# Team16_FINAL.net
KiCad netlist of a schematic drawn in EAGLE
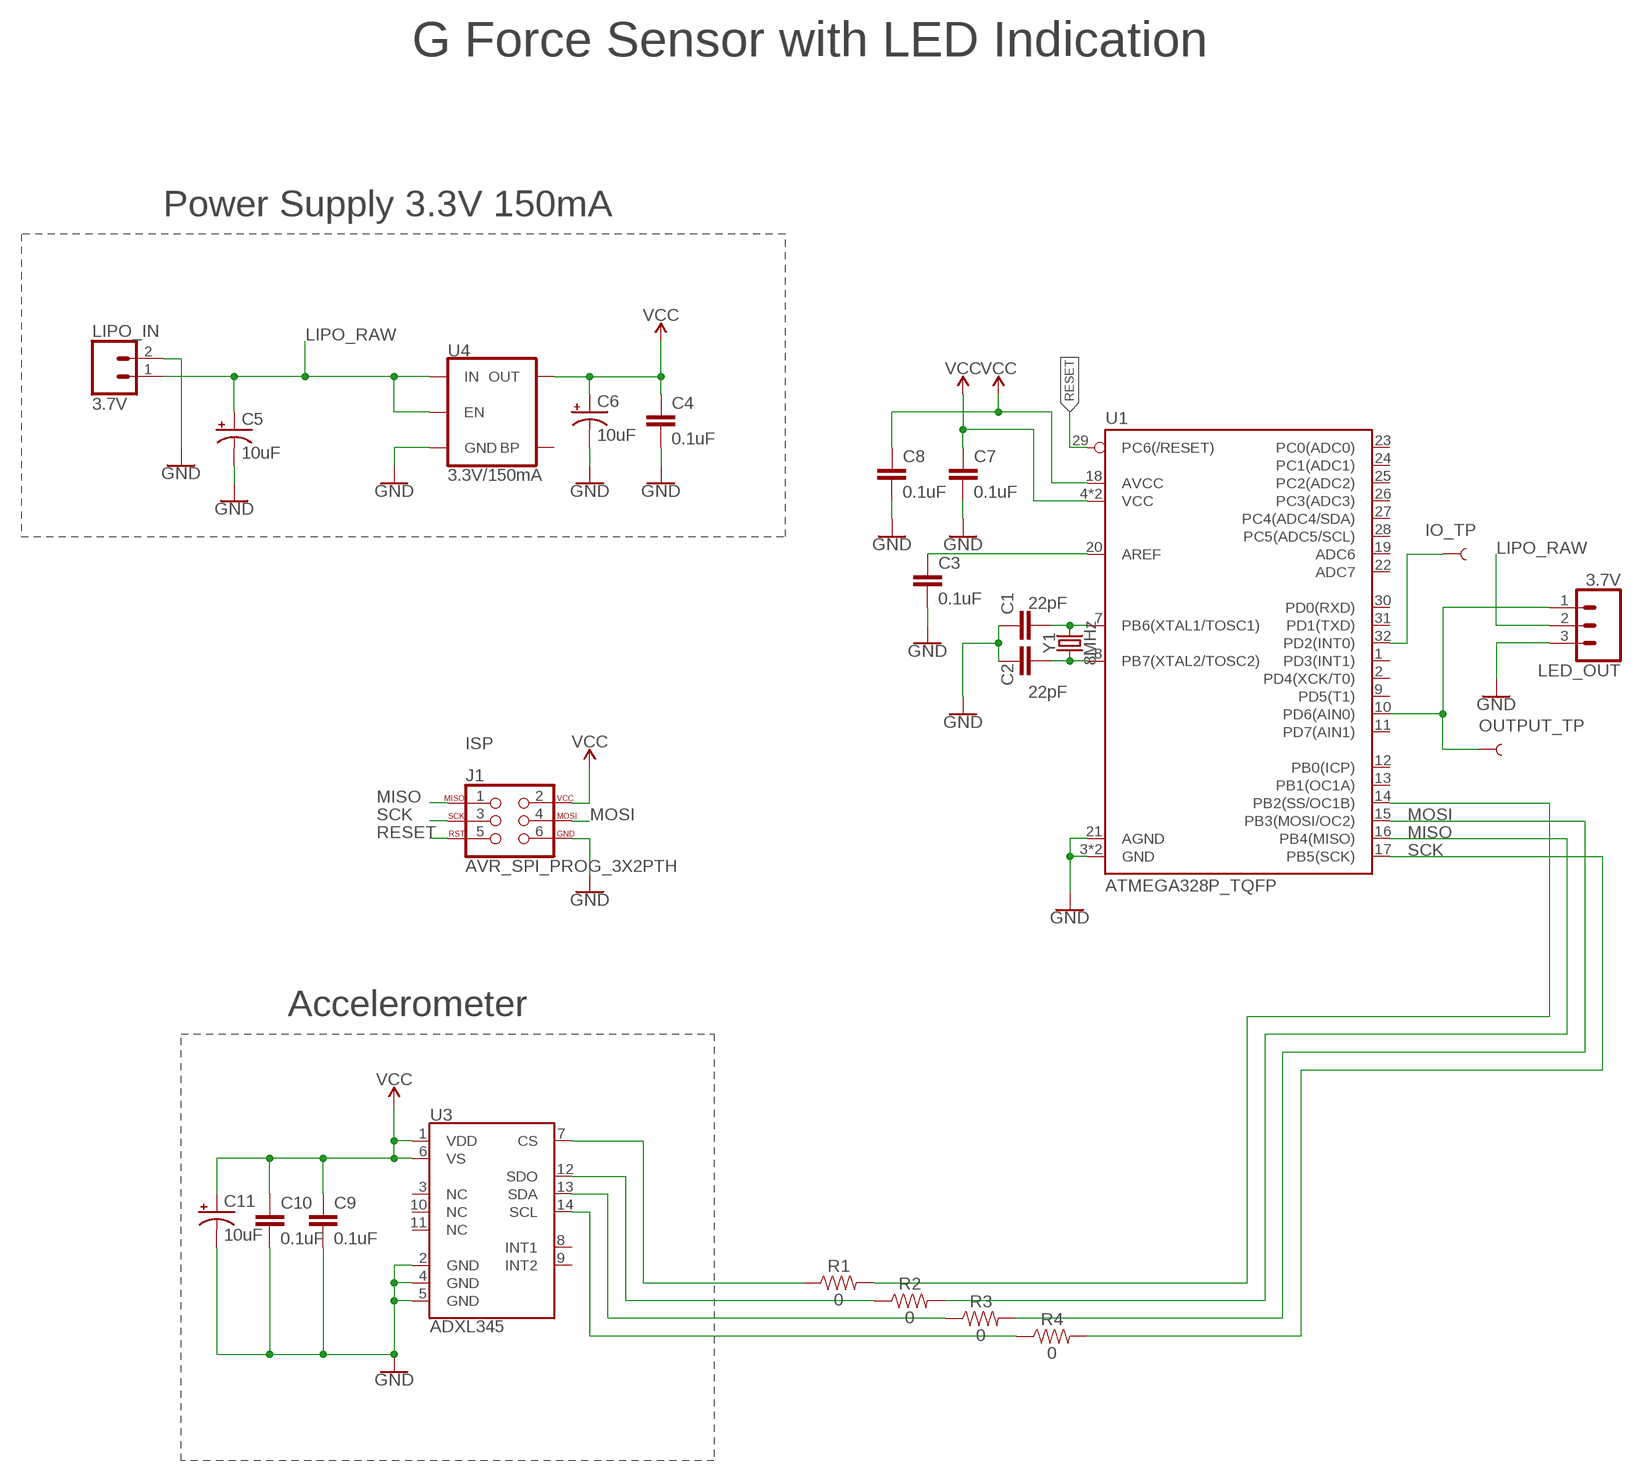
[diagram p0: schematic, sheet 1]

(export (version "E")
  (design (tool "Eeschema 10.0.6"))
  (components
    (comp (ref "C1")
      (value "22pF")
      (footprint "eagle-import:0603")
      (libsource (lib "eagle-import") (part "22PF-0603-50V-5%"))
    )
    (comp (ref "C2")
      (value "22pF")
      (footprint "eagle-import:0603")
      (libsource (lib "eagle-import") (part "22PF-0603-50V-5%"))
    )
    (comp (ref "C3")
      (value "0.1uF")
      (footprint "eagle-import:0402")
      (libsource (lib "eagle-import") (part "0.1UF-0402-16V-10%"))
    )
    (comp (ref "C4")
      (value "0.1uF")
      (footprint "eagle-import:0402")
      (libsource (lib "eagle-import") (part "0.1UF-0402-16V-10%"))
    )
    (comp (ref "C5")
      (value "10uF")
      (footprint "eagle-import:0603-POLAR")
      (libsource (lib "eagle-import") (part "10UF-POLAR-0603-6.3V-20%(TANT)"))
    )
    (comp (ref "C6")
      (value "10uF")
      (footprint "eagle-import:0603-POLAR")
      (libsource (lib "eagle-import") (part "10UF-POLAR-0603-6.3V-20%(TANT)"))
    )
    (comp (ref "C7")
      (value "0.1uF")
      (footprint "eagle-import:0402")
      (libsource (lib "eagle-import") (part "0.1UF-0402-16V-10%"))
    )
    (comp (ref "C8")
      (value "0.1uF")
      (footprint "eagle-import:0402")
      (libsource (lib "eagle-import") (part "0.1UF-0402-16V-10%"))
    )
    (comp (ref "C9")
      (value "0.1uF")
      (footprint "eagle-import:0402")
      (libsource (lib "eagle-import") (part "0.1UF-0402-16V-10%"))
    )
    (comp (ref "C10")
      (value "0.1uF")
      (footprint "eagle-import:0402")
      (libsource (lib "eagle-import") (part "0.1UF-0402-16V-10%"))
    )
    (comp (ref "C11")
      (value "10uF")
      (footprint "eagle-import:0603-POLAR")
      (libsource (lib "eagle-import") (part "10UF-POLAR-0603-6.3V-20%(TANT)"))
    )
    (comp (ref "IO_TP")
      (value "TEST-POINT3")
      (footprint "eagle-import:PAD.03X.03")
      (libsource (lib "eagle-import") (part "TEST-POINT3"))
    )
    (comp (ref "J1")
      (value "AVR_SPI_PROG_3X2PTH")
      (footprint "eagle-import:2X3")
      (libsource (lib "eagle-import") (part "AVR_SPI_PROG_3X2PTH"))
    )
    (comp (ref "LED_OUT")
      (value "3.7V")
      (footprint "eagle-import:1X03_LOCK_LONGPADS")
      (libsource (lib "eagle-import") (part "CONN_03LOCK_LONGPADS"))
    )
    (comp (ref "LIPO_IN")
      (value "3.7V")
      (footprint "eagle-import:1X02_LONGPADS")
      (libsource (lib "eagle-import") (part "CONN_02PTH3"))
    )
    (comp (ref "OUTPUT_TP")
      (value "TEST-POINT3")
      (footprint "eagle-import:PAD.03X.03")
      (libsource (lib "eagle-import") (part "TEST-POINT3"))
    )
    (comp (ref "R1")
      (value "0")
      (footprint "eagle-import:0402")
      (libsource (lib "eagle-import") (part "0OHM-0402-1/10W"))
    )
    (comp (ref "R2")
      (value "0")
      (footprint "eagle-import:0402")
      (libsource (lib "eagle-import") (part "0OHM-0402-1/10W"))
    )
    (comp (ref "R3")
      (value "0")
      (footprint "eagle-import:0402")
      (libsource (lib "eagle-import") (part "0OHM-0402-1/10W"))
    )
    (comp (ref "R4")
      (value "0")
      (footprint "eagle-import:0402")
      (libsource (lib "eagle-import") (part "0OHM-0402-1/10W"))
    )
    (comp (ref "U1")
      (value "ATMEGA328P_TQFP")
      (footprint "eagle-import:TQFP32-08")
      (libsource (lib "eagle-import") (part "ATMEGA328P_TQFP"))
    )
    (comp (ref "U3")
      (value "ADXL345")
      (footprint "eagle-import:LGA-14")
      (libsource (lib "eagle-import") (part "ADXL345"))
    )
    (comp (ref "U4")
      (value "3.3V/150mA")
      (footprint "eagle-import:SOT23-5")
      (libsource (lib "eagle-import") (part "V_REG_MIC52053.3V"))
    )
    (comp (ref "Y1")
      (value "8MHz")
      (footprint "eagle-import:CRYSTAL-SMD-5X3.2-4PAD")
      (libsource (lib "eagle-import") (part "CRYSTAL-8MHZSMD-5X3.2"))
    )
  )
  (nets
    (net (code "1") (name "/LIPO_RAW") (class "Default")
      (node (ref "C5") (pin "+") (pinfunction "+_+") (pintype "passive"))
      (node (ref "LED_OUT") (pin "2") (pinfunction "2_2") (pintype "passive"))
      (node (ref "LIPO_IN") (pin "1") (pinfunction "1_1") (pintype "passive"))
      (node (ref "U4") (pin "1") (pinfunction "IN_1") (pintype "input"))
      (node (ref "U4") (pin "3") (pinfunction "EN_3") (pintype "input"))
    )
    (net (code "2") (name "/MISO") (class "Default")
      (node (ref "J1") (pin "1") (pinfunction "1_1") (pintype "passive"))
      (node (ref "R2") (pin "2") (pinfunction "2_2") (pintype "passive"))
      (node (ref "U1") (pin "16") (pinfunction "PB4(MISO)_16") (pintype "bidirectional"))
    )
    (net (code "3") (name "/MOSI") (class "Default")
      (node (ref "J1") (pin "4") (pinfunction "4_4") (pintype "passive"))
      (node (ref "R3") (pin "2") (pinfunction "2_2") (pintype "passive"))
      (node (ref "U1") (pin "15") (pinfunction "PB3(MOSI/OC2)_15") (pintype "bidirectional"))
    )
    (net (code "4") (name "/SCK") (class "Default")
      (node (ref "J1") (pin "3") (pinfunction "3_3") (pintype "passive"))
      (node (ref "R4") (pin "2") (pinfunction "2_2") (pintype "passive"))
      (node (ref "U1") (pin "17") (pinfunction "PB5(SCK)_17") (pintype "bidirectional"))
    )
    (net (code "5") (name "GND") (class "Default")
      (node (ref "C1") (pin "1") (pinfunction "1_1") (pintype "passive"))
      (node (ref "C10") (pin "2") (pinfunction "2_2") (pintype "passive"))
      (node (ref "C11") (pin "-") (pinfunction "-_-") (pintype "passive"))
      (node (ref "C2") (pin "1") (pinfunction "1_1") (pintype "passive"))
      (node (ref "C3") (pin "2") (pinfunction "2_2") (pintype "passive"))
      (node (ref "C4") (pin "2") (pinfunction "2_2") (pintype "passive"))
      (node (ref "C5") (pin "-") (pinfunction "-_-") (pintype "passive"))
      (node (ref "C6") (pin "-") (pinfunction "-_-") (pintype "passive"))
      (node (ref "C7") (pin "2") (pinfunction "2_2") (pintype "passive"))
      (node (ref "C8") (pin "2") (pinfunction "2_2") (pintype "passive"))
      (node (ref "C9") (pin "2") (pinfunction "2_2") (pintype "passive"))
      (node (ref "J1") (pin "6") (pinfunction "6_6") (pintype "passive"))
      (node (ref "LED_OUT") (pin "3") (pinfunction "3_3") (pintype "passive"))
      (node (ref "LIPO_IN") (pin "2") (pinfunction "2_2") (pintype "passive"))
      (node (ref "U1") (pin "21") (pinfunction "AGND_21") (pintype "bidirectional"))
      (node (ref "U1") (pin "3") (pinfunction "GND_3") (pintype "bidirectional"))
      (node (ref "U1") (pin "5") (pinfunction "GND_5") (pintype "bidirectional"))
      (node (ref "U3") (pin "2") (pinfunction "GND_2") (pintype "bidirectional"))
      (node (ref "U3") (pin "4") (pinfunction "GND_4") (pintype "bidirectional"))
      (node (ref "U3") (pin "5") (pinfunction "GND_5") (pintype "bidirectional"))
      (node (ref "U4") (pin "2") (pinfunction "GND_2") (pintype "input"))
    )
    (net (code "6") (name "Net-(IO_TP-1)") (class "Default")
      (node (ref "IO_TP") (pin "P$1") (pinfunction "1_P$1") (pintype "bidirectional"))
      (node (ref "U1") (pin "32") (pinfunction "PD2(INT0)_32") (pintype "bidirectional"))
    )
    (net (code "7") (name "Net-(OUTPUT_TP-1)") (class "Default")
      (node (ref "LED_OUT") (pin "1") (pinfunction "1_1") (pintype "passive"))
      (node (ref "OUTPUT_TP") (pin "P$1") (pinfunction "1_P$1") (pintype "bidirectional"))
      (node (ref "U1") (pin "10") (pinfunction "PD6(AIN0)_10") (pintype "bidirectional"))
    )
    (net (code "8") (name "Net-(U1-AREF)") (class "Default")
      (node (ref "C3") (pin "1") (pinfunction "1_1") (pintype "passive"))
      (node (ref "U1") (pin "20") (pinfunction "AREF_20") (pintype "bidirectional"))
    )
    (net (code "9") (name "Net-(U1-PB2(SS{slash}OC1B))") (class "Default")
      (node (ref "R1") (pin "2") (pinfunction "2_2") (pintype "passive"))
      (node (ref "U1") (pin "14") (pinfunction "PB2(SS/OC1B)_14") (pintype "bidirectional"))
    )
    (net (code "10") (name "Net-(U1-PB6(XTAL1{slash}TOSC1))") (class "Default")
      (node (ref "C1") (pin "2") (pinfunction "2_2") (pintype "passive"))
      (node (ref "U1") (pin "7") (pinfunction "PB6(XTAL1/TOSC1)_7") (pintype "bidirectional"))
      (node (ref "Y1") (pin "3") (pinfunction "2_3") (pintype "passive"))
    )
    (net (code "11") (name "Net-(U1-PB7(XTAL2{slash}TOSC2))") (class "Default")
      (node (ref "C2") (pin "2") (pinfunction "2_2") (pintype "passive"))
      (node (ref "U1") (pin "8") (pinfunction "PB7(XTAL2/TOSC2)_8") (pintype "bidirectional"))
      (node (ref "Y1") (pin "1") (pinfunction "1_1") (pintype "passive"))
    )
    (net (code "12") (name "Net-(U3-CS)") (class "Default")
      (node (ref "R1") (pin "1") (pinfunction "1_1") (pintype "passive"))
      (node (ref "U3") (pin "7") (pinfunction "CS_7") (pintype "bidirectional"))
    )
    (net (code "13") (name "Net-(U3-SCL)") (class "Default")
      (node (ref "R4") (pin "1") (pinfunction "1_1") (pintype "passive"))
      (node (ref "U3") (pin "14") (pinfunction "SCL_14") (pintype "bidirectional"))
    )
    (net (code "14") (name "Net-(U3-SDA)") (class "Default")
      (node (ref "R3") (pin "1") (pinfunction "1_1") (pintype "passive"))
      (node (ref "U3") (pin "13") (pinfunction "SDA_13") (pintype "bidirectional"))
    )
    (net (code "15") (name "Net-(U3-SDO)") (class "Default")
      (node (ref "R2") (pin "1") (pinfunction "1_1") (pintype "passive"))
      (node (ref "U3") (pin "12") (pinfunction "SDO_12") (pintype "bidirectional"))
    )
    (net (code "16") (name "RESET") (class "Default")
      (node (ref "J1") (pin "5") (pinfunction "5_5") (pintype "passive"))
      (node (ref "U1") (pin "29") (pinfunction "PC6(/RESET)_29") (pintype "bidirectional"))
    )
    (net (code "17") (name "VCC") (class "Default")
      (node (ref "C10") (pin "1") (pinfunction "1_1") (pintype "passive"))
      (node (ref "C11") (pin "+") (pinfunction "+_+") (pintype "passive"))
      (node (ref "C4") (pin "1") (pinfunction "1_1") (pintype "passive"))
      (node (ref "C6") (pin "+") (pinfunction "+_+") (pintype "passive"))
      (node (ref "C7") (pin "1") (pinfunction "1_1") (pintype "passive"))
      (node (ref "C8") (pin "1") (pinfunction "1_1") (pintype "passive"))
      (node (ref "C9") (pin "1") (pinfunction "1_1") (pintype "passive"))
      (node (ref "J1") (pin "2") (pinfunction "2_2") (pintype "passive"))
      (node (ref "U1") (pin "18") (pinfunction "AVCC_18") (pintype "bidirectional"))
      (node (ref "U1") (pin "4") (pinfunction "VCC_4") (pintype "bidirectional"))
      (node (ref "U1") (pin "6") (pinfunction "VCC_6") (pintype "bidirectional"))
      (node (ref "U3") (pin "1") (pinfunction "VDD_1") (pintype "bidirectional"))
      (node (ref "U3") (pin "6") (pinfunction "VS_6") (pintype "bidirectional"))
      (node (ref "U4") (pin "5") (pinfunction "OUT_5") (pintype "passive"))
    )
    (net (code "18") (name "unconnected-(U1-ADC6-Pad19)") (class "Default")
      (node (ref "U1") (pin "19") (pinfunction "ADC6_19") (pintype "bidirectional"))
    )
    (net (code "19") (name "unconnected-(U1-ADC7-Pad22)") (class "Default")
      (node (ref "U1") (pin "22") (pinfunction "ADC7_22") (pintype "bidirectional"))
    )
    (net (code "20") (name "unconnected-(U1-PB0(ICP)-Pad12)") (class "Default")
      (node (ref "U1") (pin "12") (pinfunction "PB0(ICP)_12") (pintype "bidirectional"))
    )
    (net (code "21") (name "unconnected-(U1-PB1(OC1A)-Pad13)") (class "Default")
      (node (ref "U1") (pin "13") (pinfunction "PB1(OC1A)_13") (pintype "bidirectional"))
    )
    (net (code "22") (name "unconnected-(U1-PC0(ADC0)-Pad23)") (class "Default")
      (node (ref "U1") (pin "23") (pinfunction "PC0(ADC0)_23") (pintype "bidirectional"))
    )
    (net (code "23") (name "unconnected-(U1-PC1(ADC1)-Pad24)") (class "Default")
      (node (ref "U1") (pin "24") (pinfunction "PC1(ADC1)_24") (pintype "bidirectional"))
    )
    (net (code "24") (name "unconnected-(U1-PC2(ADC2)-Pad25)") (class "Default")
      (node (ref "U1") (pin "25") (pinfunction "PC2(ADC2)_25") (pintype "bidirectional"))
    )
    (net (code "25") (name "unconnected-(U1-PC3(ADC3)-Pad26)") (class "Default")
      (node (ref "U1") (pin "26") (pinfunction "PC3(ADC3)_26") (pintype "bidirectional"))
    )
    (net (code "26") (name "unconnected-(U1-PC4(ADC4{slash}SDA)-Pad27)") (class "Default")
      (node (ref "U1") (pin "27") (pinfunction "PC4(ADC4/SDA)_27") (pintype "bidirectional"))
    )
    (net (code "27") (name "unconnected-(U1-PC5(ADC5{slash}SCL)-Pad28)") (class "Default")
      (node (ref "U1") (pin "28") (pinfunction "PC5(ADC5/SCL)_28") (pintype "bidirectional"))
    )
    (net (code "28") (name "unconnected-(U1-PD0(RXD)-Pad30)") (class "Default")
      (node (ref "U1") (pin "30") (pinfunction "PD0(RXD)_30") (pintype "bidirectional"))
    )
    (net (code "29") (name "unconnected-(U1-PD1(TXD)-Pad31)") (class "Default")
      (node (ref "U1") (pin "31") (pinfunction "PD1(TXD)_31") (pintype "bidirectional"))
    )
    (net (code "30") (name "unconnected-(U1-PD3(INT1)-Pad1)") (class "Default")
      (node (ref "U1") (pin "1") (pinfunction "PD3(INT1)_1") (pintype "bidirectional"))
    )
    (net (code "31") (name "unconnected-(U1-PD4(XCK{slash}T0)-Pad2)") (class "Default")
      (node (ref "U1") (pin "2") (pinfunction "PD4(XCK/T0)_2") (pintype "bidirectional"))
    )
    (net (code "32") (name "unconnected-(U1-PD5(T1)-Pad9)") (class "Default")
      (node (ref "U1") (pin "9") (pinfunction "PD5(T1)_9") (pintype "bidirectional"))
    )
    (net (code "33") (name "unconnected-(U1-PD7(AIN1)-Pad11)") (class "Default")
      (node (ref "U1") (pin "11") (pinfunction "PD7(AIN1)_11") (pintype "bidirectional"))
    )
    (net (code "34") (name "unconnected-(U3-INT1-Pad8)") (class "Default")
      (node (ref "U3") (pin "8") (pinfunction "INT1_8") (pintype "bidirectional"))
    )
    (net (code "35") (name "unconnected-(U3-INT2-Pad9)") (class "Default")
      (node (ref "U3") (pin "9") (pinfunction "INT2_9") (pintype "bidirectional"))
    )
    (net (code "36") (name "unconnected-(U3-NC-Pad3)") (class "Default")
      (node (ref "U3") (pin "3") (pinfunction "NC_3") (pintype "bidirectional"))
    )
    (net (code "37") (name "unconnected-(U3-NC-Pad10)") (class "Default")
      (node (ref "U3") (pin "10") (pinfunction "NC_10") (pintype "bidirectional"))
    )
    (net (code "38") (name "unconnected-(U3-NC-Pad11)") (class "Default")
      (node (ref "U3") (pin "11") (pinfunction "NC_11") (pintype "bidirectional"))
    )
    (net (code "39") (name "unconnected-(U4-BP-Pad4)") (class "Default")
      (node (ref "U4") (pin "4") (pinfunction "BP_4") (pintype "input"))
    )
  )
)
